# S29GL064N90TFI04.net
KiCad netlist of a schematic drawn in Altium Designer
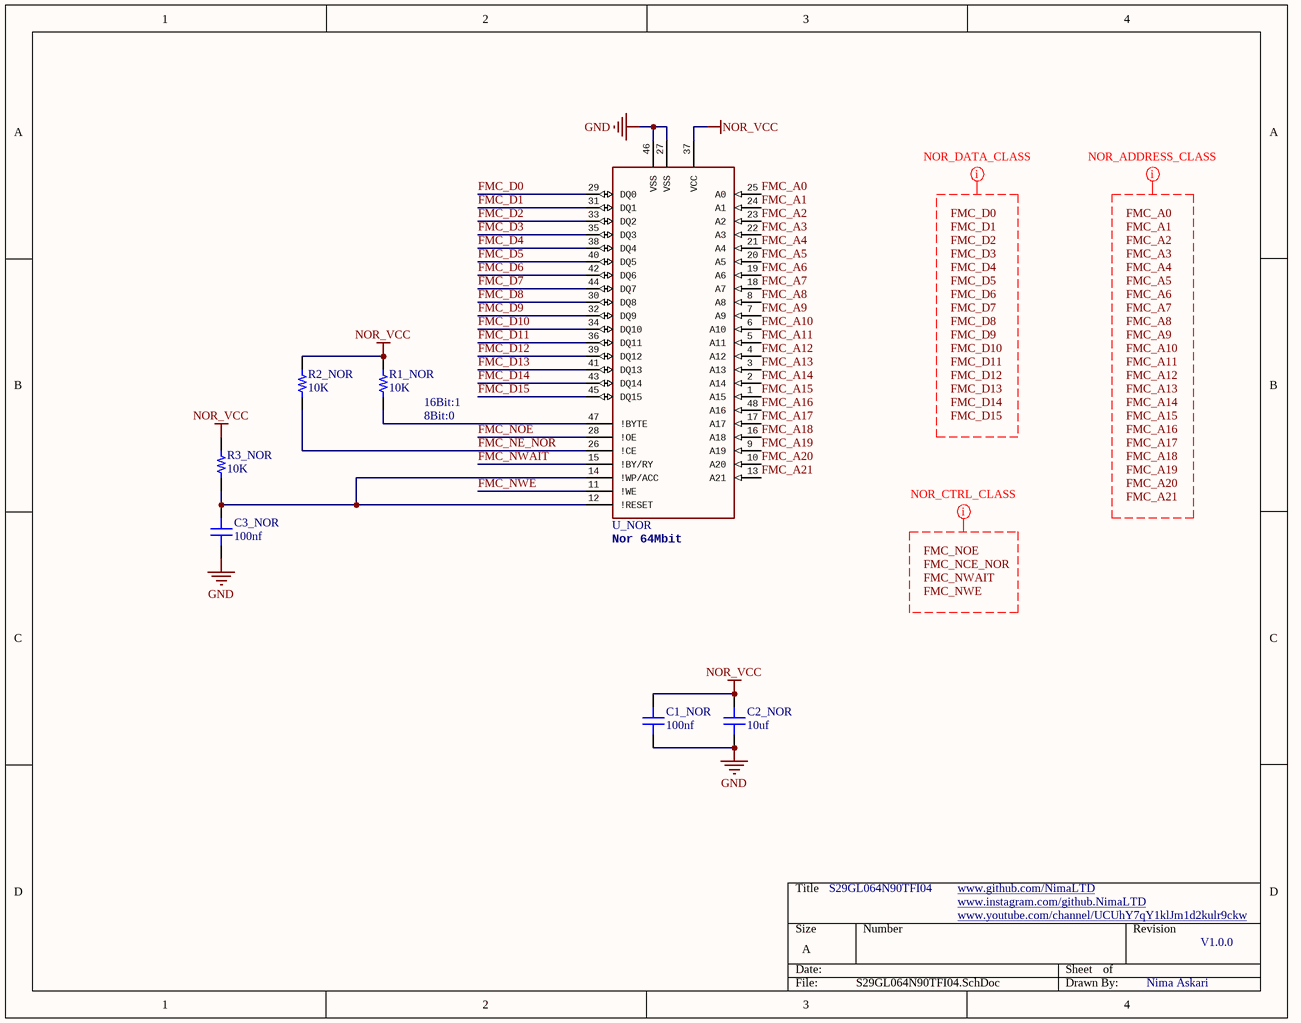
[diagram p0: S29GL064N90TFI04.SchDoc]

(export (version "E")
  (design (tool "Eeschema 10.0.6"))
  (components
    (comp (ref "C1_NOR")
      (value "100nf")
      (footprint "CAP 0805")
      (description "SMT Capacitor")
      (libsource (lib "CAPACITOR") (part "Cap SMD 0805"))
    )
    (comp (ref "C2_NOR")
      (value "10uf")
      (footprint "CAP 0805")
      (description "SMT Capacitor")
      (libsource (lib "CAPACITOR") (part "Cap SMD 0805"))
    )
    (comp (ref "C3_NOR")
      (value "100nf")
      (footprint "CAP 0805")
      (description "SMT Capacitor")
      (libsource (lib "CAPACITOR") (part "Cap SMD 0805"))
    )
    (comp (ref "R1_NOR")
      (value "10K")
      (footprint "RES 0805")
      (description "SMD Resistor")
      (libsource (lib "RESISTOR") (part "Res SMD 0805"))
    )
    (comp (ref "R2_NOR")
      (value "10K")
      (footprint "RES 0805")
      (description "SMD Resistor")
      (libsource (lib "RESISTOR") (part "Res SMD 0805"))
    )
    (comp (ref "R3_NOR")
      (value "10K")
      (footprint "RES 0805")
      (description "SMD Resistor")
      (libsource (lib "RESISTOR") (part "Res SMD 0805"))
    )
    (comp (ref "U_NOR")
      (value "Nor 64Mbit")
      (footprint "TSOP48")
      (libsource (lib "IC") (part "S29GL064N90TFI04"))
    )
  )
  (nets
    (net (code "1") (name "/FMC_A0") (class "Default")
      (node (ref "U_NOR") (pin "25") (pinfunction "A0_25") (pintype "input"))
    )
    (net (code "2") (name "/FMC_A1") (class "Default")
      (node (ref "U_NOR") (pin "24") (pinfunction "A1_24") (pintype "input"))
    )
    (net (code "3") (name "/FMC_A2") (class "Default")
      (node (ref "U_NOR") (pin "23") (pinfunction "A2_23") (pintype "input"))
    )
    (net (code "4") (name "/FMC_A3") (class "Default")
      (node (ref "U_NOR") (pin "22") (pinfunction "A3_22") (pintype "input"))
    )
    (net (code "5") (name "/FMC_A4") (class "Default")
      (node (ref "U_NOR") (pin "21") (pinfunction "A4_21") (pintype "input"))
    )
    (net (code "6") (name "/FMC_A5") (class "Default")
      (node (ref "U_NOR") (pin "20") (pinfunction "A5_20") (pintype "input"))
    )
    (net (code "7") (name "/FMC_A6") (class "Default")
      (node (ref "U_NOR") (pin "19") (pinfunction "A6_19") (pintype "input"))
    )
    (net (code "8") (name "/FMC_A7") (class "Default")
      (node (ref "U_NOR") (pin "18") (pinfunction "A7_18") (pintype "input"))
    )
    (net (code "9") (name "/FMC_A8") (class "Default")
      (node (ref "U_NOR") (pin "8") (pinfunction "A8_8") (pintype "input"))
    )
    (net (code "10") (name "/FMC_A9") (class "Default")
      (node (ref "U_NOR") (pin "7") (pinfunction "A9_7") (pintype "input"))
    )
    (net (code "11") (name "/FMC_A10") (class "Default")
      (node (ref "U_NOR") (pin "6") (pinfunction "A10_6") (pintype "input"))
    )
    (net (code "12") (name "/FMC_A11") (class "Default")
      (node (ref "U_NOR") (pin "5") (pinfunction "A11_5") (pintype "input"))
    )
    (net (code "13") (name "/FMC_A12") (class "Default")
      (node (ref "U_NOR") (pin "4") (pinfunction "A12_4") (pintype "input"))
    )
    (net (code "14") (name "/FMC_A13") (class "Default")
      (node (ref "U_NOR") (pin "3") (pinfunction "A13_3") (pintype "input"))
    )
    (net (code "15") (name "/FMC_A14") (class "Default")
      (node (ref "U_NOR") (pin "2") (pinfunction "A14_2") (pintype "input"))
    )
    (net (code "16") (name "/FMC_A15") (class "Default")
      (node (ref "U_NOR") (pin "1") (pinfunction "A15_1") (pintype "input"))
    )
    (net (code "17") (name "/FMC_A16") (class "Default")
      (node (ref "U_NOR") (pin "48") (pinfunction "A16_48") (pintype "input"))
    )
    (net (code "18") (name "/FMC_A17") (class "Default")
      (node (ref "U_NOR") (pin "17") (pinfunction "A17_17") (pintype "input"))
    )
    (net (code "19") (name "/FMC_A18") (class "Default")
      (node (ref "U_NOR") (pin "16") (pinfunction "A18_16") (pintype "input"))
    )
    (net (code "20") (name "/FMC_A19") (class "Default")
      (node (ref "U_NOR") (pin "9") (pinfunction "A19_9") (pintype "input"))
    )
    (net (code "21") (name "/FMC_A20") (class "Default")
      (node (ref "U_NOR") (pin "10") (pinfunction "A20_10") (pintype "input"))
    )
    (net (code "22") (name "/FMC_A21") (class "Default")
      (node (ref "U_NOR") (pin "13") (pinfunction "A21_13") (pintype "input"))
    )
    (net (code "23") (name "/FMC_D0") (class "Default")
      (node (ref "U_NOR") (pin "29") (pinfunction "DQ0_29") (pintype "bidirectional"))
    )
    (net (code "24") (name "/FMC_D1") (class "Default")
      (node (ref "U_NOR") (pin "31") (pinfunction "DQ1_31") (pintype "bidirectional"))
    )
    (net (code "25") (name "/FMC_D2") (class "Default")
      (node (ref "U_NOR") (pin "33") (pinfunction "DQ2_33") (pintype "bidirectional"))
    )
    (net (code "26") (name "/FMC_D3") (class "Default")
      (node (ref "U_NOR") (pin "35") (pinfunction "DQ3_35") (pintype "bidirectional"))
    )
    (net (code "27") (name "/FMC_D4") (class "Default")
      (node (ref "U_NOR") (pin "38") (pinfunction "DQ4_38") (pintype "bidirectional"))
    )
    (net (code "28") (name "/FMC_D5") (class "Default")
      (node (ref "U_NOR") (pin "40") (pinfunction "DQ5_40") (pintype "bidirectional"))
    )
    (net (code "29") (name "/FMC_D6") (class "Default")
      (node (ref "U_NOR") (pin "42") (pinfunction "DQ6_42") (pintype "bidirectional"))
    )
    (net (code "30") (name "/FMC_D7") (class "Default")
      (node (ref "U_NOR") (pin "44") (pinfunction "DQ7_44") (pintype "bidirectional"))
    )
    (net (code "31") (name "/FMC_D8") (class "Default")
      (node (ref "U_NOR") (pin "30") (pinfunction "DQ8_30") (pintype "bidirectional"))
    )
    (net (code "32") (name "/FMC_D9") (class "Default")
      (node (ref "U_NOR") (pin "32") (pinfunction "DQ9_32") (pintype "bidirectional"))
    )
    (net (code "33") (name "/FMC_D10") (class "Default")
      (node (ref "U_NOR") (pin "34") (pinfunction "DQ10_34") (pintype "bidirectional"))
    )
    (net (code "34") (name "/FMC_D11") (class "Default")
      (node (ref "U_NOR") (pin "36") (pinfunction "DQ11_36") (pintype "bidirectional"))
    )
    (net (code "35") (name "/FMC_D12") (class "Default")
      (node (ref "U_NOR") (pin "39") (pinfunction "DQ12_39") (pintype "bidirectional"))
    )
    (net (code "36") (name "/FMC_D13") (class "Default")
      (node (ref "U_NOR") (pin "41") (pinfunction "DQ13_41") (pintype "bidirectional"))
    )
    (net (code "37") (name "/FMC_D14") (class "Default")
      (node (ref "U_NOR") (pin "43") (pinfunction "DQ14_43") (pintype "bidirectional"))
    )
    (net (code "38") (name "/FMC_D15") (class "Default")
      (node (ref "U_NOR") (pin "45") (pinfunction "DQ15_45") (pintype "bidirectional"))
    )
    (net (code "40") (name "/FMC_NE_NOR") (class "Default")
      (node (ref "R2_NOR") (pin "1") (pinfunction "1_1") (pintype "passive"))
      (node (ref "U_NOR") (pin "26") (pinfunction "!CE_26") (pintype "passive"))
    )
    (net (code "41") (name "/FMC_NOE") (class "Default")
      (node (ref "U_NOR") (pin "28") (pinfunction "!OE_28") (pintype "passive"))
    )
    (net (code "42") (name "/FMC_NWAIT") (class "Default")
      (node (ref "U_NOR") (pin "15") (pinfunction "!BY/RY_15") (pintype "passive"))
    )
    (net (code "43") (name "/FMC_NWE") (class "Default")
      (node (ref "U_NOR") (pin "11") (pinfunction "!WE_11") (pintype "passive"))
    )
    (net (code "44") (name "GND") (class "Default")
      (node (ref "C1_NOR") (pin "1") (pinfunction "1_1") (pintype "passive"))
      (node (ref "C2_NOR") (pin "1") (pinfunction "1_1") (pintype "passive"))
      (node (ref "C3_NOR") (pin "1") (pinfunction "1_1") (pintype "passive"))
      (node (ref "U_NOR") (pin "27") (pinfunction "VSS_27") (pintype "passive"))
      (node (ref "U_NOR") (pin "46") (pinfunction "VSS_46") (pintype "passive"))
    )
    (net (code "45") (name "NOR_VCC") (class "Default")
      (node (ref "C1_NOR") (pin "2") (pinfunction "2_2") (pintype "passive"))
      (node (ref "C2_NOR") (pin "2") (pinfunction "2_2") (pintype "passive"))
      (node (ref "R1_NOR") (pin "2") (pinfunction "2_2") (pintype "passive"))
      (node (ref "R2_NOR") (pin "2") (pinfunction "2_2") (pintype "passive"))
      (node (ref "R3_NOR") (pin "2") (pinfunction "2_2") (pintype "passive"))
      (node (ref "U_NOR") (pin "37") (pinfunction "VCC_37") (pintype "passive"))
    )
    (net (code "46") (name "Net-(U_NOR-!BYTE)") (class "Default")
      (node (ref "R1_NOR") (pin "1") (pinfunction "1_1") (pintype "passive"))
      (node (ref "U_NOR") (pin "47") (pinfunction "!BYTE_47") (pintype "passive"))
    )
    (net (code "47") (name "Net-(U_NOR-!RESET)") (class "Default")
      (node (ref "C3_NOR") (pin "2") (pinfunction "2_2") (pintype "passive"))
      (node (ref "R3_NOR") (pin "1") (pinfunction "1_1") (pintype "passive"))
      (node (ref "U_NOR") (pin "12") (pinfunction "!RESET_12") (pintype "passive"))
      (node (ref "U_NOR") (pin "14") (pinfunction "!WP/ACC_14") (pintype "passive"))
    )
  )
)
